# master_jorge3newIMU.net
KiCad netlist of a schematic drawn in EAGLE
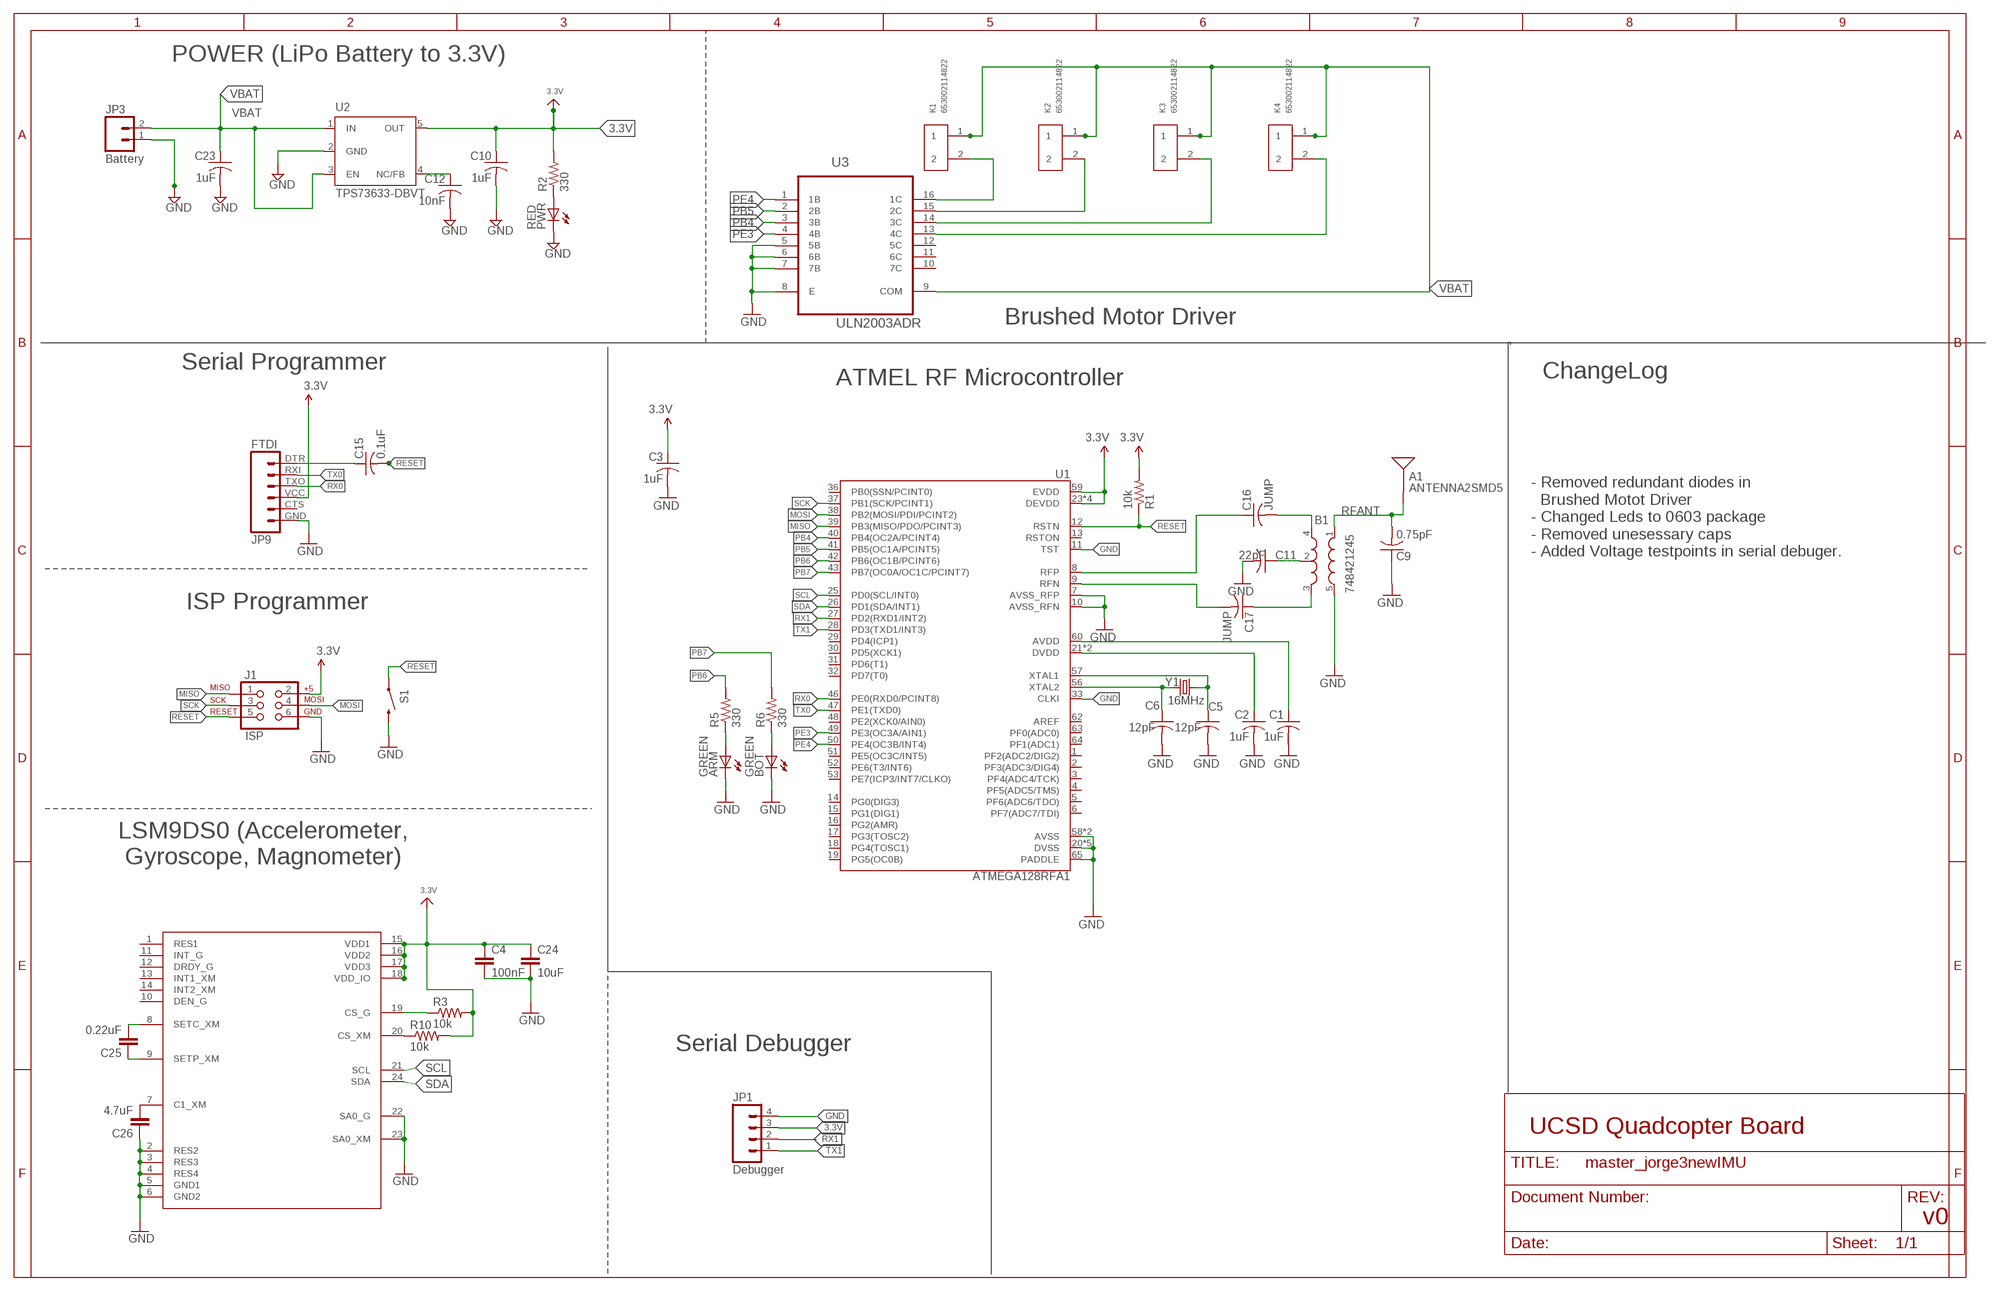
[diagram p0: schematic, sheet 1]

(export (version "E")
  (design (tool "Eeschema 10.0.6"))
  (components
    (comp (ref "A1")
      (value "ANTENNA2SMD5")
      (footprint "eagle-import:ANTENNA-CHIP5")
      (libsource (lib "eagle-import") (part "ANTENNA2SMD5"))
    )
    (comp (ref "ARM")
      (value "GREEN")
      (footprint "eagle-import:CHIP-LED0805")
      (libsource (lib "eagle-import") (part "LEDCHIP-LED0805"))
    )
    (comp (ref "B1")
      (value "748421245")
      (footprint "eagle-import:BALUN")
      (libsource (lib "eagle-import") (part "BALUN0805"))
    )
    (comp (ref "BOT")
      (value "GREEN")
      (footprint "eagle-import:CHIP-LED0805")
      (libsource (lib "eagle-import") (part "LEDCHIP-LED0805"))
    )
    (comp (ref "C1")
      (value "1uF")
      (footprint "eagle-import:C0805")
      (libsource (lib "eagle-import") (part "C-USC0805"))
    )
    (comp (ref "C2")
      (value "1uF")
      (footprint "eagle-import:C0805")
      (libsource (lib "eagle-import") (part "C-USC0805"))
    )
    (comp (ref "C3")
      (value "1uF")
      (footprint "eagle-import:C0805")
      (libsource (lib "eagle-import") (part "C-USC0805"))
    )
    (comp (ref "C4")
      (value "100nF")
      (footprint "eagle-import:0805")
      (libsource (lib "eagle-import") (part "CAP0805"))
    )
    (comp (ref "C5")
      (value "12pF")
      (footprint "eagle-import:C0805")
      (libsource (lib "eagle-import") (part "C-USC0805"))
    )
    (comp (ref "C6")
      (value "12pF")
      (footprint "eagle-import:C0805")
      (libsource (lib "eagle-import") (part "C-USC0805"))
    )
    (comp (ref "C9")
      (value "0.75pF")
      (footprint "eagle-import:C0805")
      (libsource (lib "eagle-import") (part "C-USC0805"))
    )
    (comp (ref "C10")
      (value "1uF")
      (footprint "eagle-import:C0805")
      (libsource (lib "eagle-import") (part "C-USC0805"))
    )
    (comp (ref "C11")
      (value "22pF")
      (footprint "eagle-import:C0805")
      (libsource (lib "eagle-import") (part "C-USC0805"))
    )
    (comp (ref "C12")
      (value "10nF")
      (footprint "eagle-import:C0805")
      (libsource (lib "eagle-import") (part "C-USC0805"))
    )
    (comp (ref "C15")
      (value "0.1uF")
      (footprint "eagle-import:C0805")
      (libsource (lib "eagle-import") (part "C-USC0805"))
    )
    (comp (ref "C16")
      (value "JUMP")
      (footprint "eagle-import:C0805")
      (libsource (lib "eagle-import") (part "C-USC0805"))
    )
    (comp (ref "C17")
      (value "JUMP")
      (footprint "eagle-import:C0805")
      (libsource (lib "eagle-import") (part "C-USC0805"))
    )
    (comp (ref "C23")
      (value "1uF")
      (footprint "eagle-import:C0805")
      (libsource (lib "eagle-import") (part "C-USC0805"))
    )
    (comp (ref "C24")
      (value "10uF")
      (footprint "eagle-import:0805")
      (libsource (lib "eagle-import") (part "CAP0805"))
    )
    (comp (ref "C25")
      (value "0.22uF")
      (footprint "eagle-import:0805")
      (libsource (lib "eagle-import") (part "CAP0805"))
    )
    (comp (ref "C26")
      (value "4.7uF")
      (footprint "eagle-import:0805")
      (libsource (lib "eagle-import") (part "CAP0805"))
    )
    (comp (ref "J1")
      (value "ISP")
      (footprint "eagle-import:2X3-NS")
      (libsource (lib "eagle-import") (part "AVR_SPI_PRG_6NS"))
    )
    (comp (ref "JP1")
      (value "Debugger")
      (footprint "eagle-import:1X04")
      (libsource (lib "eagle-import") (part "M04PTH"))
    )
    (comp (ref "JP3")
      (value "Battery")
      (footprint "eagle-import:1X02")
      (libsource (lib "eagle-import") (part "M02PTH"))
    )
    (comp (ref "JP9")
      (value "FTDI")
      (footprint "eagle-import:FTDI_BASIC")
      (libsource (lib "eagle-import") (part "FTDI_BASICPTH"))
    )
    (comp (ref "K1")
      (value "653002114822")
      (footprint "eagle-import:653002114822")
      (libsource (lib "eagle-import") (part "653002114822"))
    )
    (comp (ref "K2")
      (value "653002114822")
      (footprint "eagle-import:653002114822")
      (libsource (lib "eagle-import") (part "653002114822"))
    )
    (comp (ref "K3")
      (value "653002114822")
      (footprint "eagle-import:653002114822")
      (libsource (lib "eagle-import") (part "653002114822"))
    )
    (comp (ref "K4")
      (value "653002114822")
      (footprint "eagle-import:653002114822")
      (libsource (lib "eagle-import") (part "653002114822"))
    )
    (comp (ref "PWR")
      (value "RED")
      (footprint "eagle-import:CHIP-LED0805")
      (libsource (lib "eagle-import") (part "LEDCHIP-LED0805"))
    )
    (comp (ref "R1")
      (value "10k")
      (footprint "eagle-import:R0805")
      (libsource (lib "eagle-import") (part "R-US_R0805"))
    )
    (comp (ref "R2")
      (value "330")
      (footprint "eagle-import:R0805")
      (libsource (lib "eagle-import") (part "R-US_R0805"))
    )
    (comp (ref "R3")
      (value "10k")
      (footprint "eagle-import:0805")
      (libsource (lib "eagle-import") (part "RESISTOR0805-RES"))
    )
    (comp (ref "R5")
      (value "330")
      (footprint "eagle-import:R0805")
      (libsource (lib "eagle-import") (part "R-US_R0805"))
    )
    (comp (ref "R6")
      (value "330")
      (footprint "eagle-import:R0805")
      (libsource (lib "eagle-import") (part "R-US_R0805"))
    )
    (comp (ref "R10")
      (value "10k")
      (footprint "eagle-import:0805")
      (libsource (lib "eagle-import") (part "RESISTOR0805-RES"))
    )
    (comp (ref "S1")
      (value "SWITCH-MOMENTARY-2SMD")
      (footprint "eagle-import:TACTILE_SWITCH_SMD")
      (libsource (lib "eagle-import") (part "SWITCH-MOMENTARY-2SMD"))
    )
    (comp (ref "U1")
      (value "ATMEGA128RFA1")
      (footprint "eagle-import:QFN-64")
      (libsource (lib "eagle-import") (part "ATMEGA128RFA1"))
    )
    (comp (ref "U2")
      (value "TPS73633-DBVT")
      (footprint "eagle-import:SOT23-DBV")
      (libsource (lib "eagle-import") (part "TPS73633-DBVT"))
    )
    (comp (ref "U3")
      (value "ULN2003ADR")
      (footprint "eagle-import:SOIC127P600X175-16N")
      (libsource (lib "eagle-import") (part "ULN2003ADR"))
    )
    (comp (ref "U4")
      (value "LSM9DS0")
      (footprint "eagle-import:LGA-24")
      (libsource (lib "eagle-import") (part "LSM9DS0"))
    )
    (comp (ref "Y1")
      (value "16MHz")
      (footprint "eagle-import:CRYSTAL-SMD-5X3")
      (libsource (lib "eagle-import") (part "CRYSTAL5X3"))
    )
  )
  (nets
    (net (code "1") (name "/RFANT") (class "Default")
      (node (ref "A1") (pin "FEED") (pinfunction "SIGNAL_FEED") (pintype "bidirectional"))
      (node (ref "B1") (pin "1") (pinfunction "IN_1") (pintype "bidirectional"))
      (node (ref "C9") (pin "2") (pinfunction "2_2") (pintype "passive"))
    )
    (net (code "2") (name "3.3V") (class "Default")
      (node (ref "C10") (pin "1") (pinfunction "1_1") (pintype "passive"))
      (node (ref "C24") (pin "1") (pinfunction "1_1") (pintype "passive"))
      (node (ref "C3") (pin "1") (pinfunction "1_1") (pintype "passive"))
      (node (ref "C4") (pin "1") (pinfunction "1_1") (pintype "passive"))
      (node (ref "J1") (pin "2") (pinfunction "2_2") (pintype "passive"))
      (node (ref "JP1") (pin "3") (pinfunction "3_3") (pintype "passive"))
      (node (ref "JP9") (pin "VCC") (pinfunction "4_VCC") (pintype "passive"))
      (node (ref "R1") (pin "2") (pinfunction "2_2") (pintype "passive"))
      (node (ref "R10") (pin "2") (pinfunction "2_2") (pintype "passive"))
      (node (ref "R2") (pin "2") (pinfunction "2_2") (pintype "passive"))
      (node (ref "R3") (pin "2") (pinfunction "2_2") (pintype "passive"))
      (node (ref "U1") (pin "23") (pinfunction "DEVDD_23") (pintype "bidirectional"))
      (node (ref "U1") (pin "34") (pinfunction "DEVDD_34") (pintype "bidirectional"))
      (node (ref "U1") (pin "44") (pinfunction "DEVDD_44") (pintype "bidirectional"))
      (node (ref "U1") (pin "54") (pinfunction "DEVDD_54") (pintype "bidirectional"))
      (node (ref "U1") (pin "59") (pinfunction "EVDD_59") (pintype "bidirectional"))
      (node (ref "U2") (pin "5") (pinfunction "OUT_5") (pintype "passive"))
      (node (ref "U4") (pin "15") (pinfunction "VDD1_15") (pintype "bidirectional"))
      (node (ref "U4") (pin "16") (pinfunction "VDD2_16") (pintype "bidirectional"))
      (node (ref "U4") (pin "17") (pinfunction "VDD3_17") (pintype "bidirectional"))
      (node (ref "U4") (pin "18") (pinfunction "VDD_IO_18") (pintype "bidirectional"))
    )
    (net (code "3") (name "GND") (class "Default")
      (node (ref "ARM") (pin "C") (pinfunction "C_C") (pintype "passive"))
      (node (ref "B1") (pin "5") (pinfunction "GND_5") (pintype "bidirectional"))
      (node (ref "BOT") (pin "C") (pinfunction "C_C") (pintype "passive"))
      (node (ref "C1") (pin "2") (pinfunction "2_2") (pintype "passive"))
      (node (ref "C10") (pin "2") (pinfunction "2_2") (pintype "passive"))
      (node (ref "C11") (pin "2") (pinfunction "2_2") (pintype "passive"))
      (node (ref "C12") (pin "2") (pinfunction "2_2") (pintype "passive"))
      (node (ref "C2") (pin "2") (pinfunction "2_2") (pintype "passive"))
      (node (ref "C23") (pin "2") (pinfunction "2_2") (pintype "passive"))
      (node (ref "C24") (pin "2") (pinfunction "2_2") (pintype "passive"))
      (node (ref "C26") (pin "1") (pinfunction "1_1") (pintype "passive"))
      (node (ref "C3") (pin "2") (pinfunction "2_2") (pintype "passive"))
      (node (ref "C4") (pin "2") (pinfunction "2_2") (pintype "passive"))
      (node (ref "C5") (pin "2") (pinfunction "2_2") (pintype "passive"))
      (node (ref "C6") (pin "2") (pinfunction "2_2") (pintype "passive"))
      (node (ref "C9") (pin "1") (pinfunction "1_1") (pintype "passive"))
      (node (ref "J1") (pin "6") (pinfunction "6_6") (pintype "passive"))
      (node (ref "JP1") (pin "4") (pinfunction "4_4") (pintype "passive"))
      (node (ref "JP3") (pin "1") (pinfunction "1_1") (pintype "passive"))
      (node (ref "JP9") (pin "GND") (pinfunction "6_GND") (pintype "passive"))
      (node (ref "PWR") (pin "C") (pinfunction "C_C") (pintype "passive"))
      (node (ref "S1") (pin "3") (pinfunction "2_3") (pintype "passive"))
      (node (ref "U1") (pin "10") (pinfunction "AVSS_RFN_10") (pintype "bidirectional"))
      (node (ref "U1") (pin "11") (pinfunction "TST_11") (pintype "bidirectional"))
      (node (ref "U1") (pin "20") (pinfunction "DVSS_20") (pintype "bidirectional"))
      (node (ref "U1") (pin "24") (pinfunction "DVSS_24") (pintype "bidirectional"))
      (node (ref "U1") (pin "33") (pinfunction "CLKI_33") (pintype "bidirectional"))
      (node (ref "U1") (pin "35") (pinfunction "DVSS_35") (pintype "bidirectional"))
      (node (ref "U1") (pin "45") (pinfunction "DVSS_45") (pintype "bidirectional"))
      (node (ref "U1") (pin "55") (pinfunction "DVSS_55") (pintype "bidirectional"))
      (node (ref "U1") (pin "58") (pinfunction "AVSS_58") (pintype "bidirectional"))
      (node (ref "U1") (pin "61") (pinfunction "AVSS_61") (pintype "bidirectional"))
      (node (ref "U1") (pin "65") (pinfunction "PADDLE_65") (pintype "bidirectional"))
      (node (ref "U1") (pin "7") (pinfunction "AVSS_RFP_7") (pintype "bidirectional"))
      (node (ref "U2") (pin "2") (pinfunction "GND_2") (pintype "input"))
      (node (ref "U3") (pin "5") (pinfunction "5B_5") (pintype "input"))
      (node (ref "U3") (pin "6") (pinfunction "6B_6") (pintype "input"))
      (node (ref "U3") (pin "7") (pinfunction "7B_7") (pintype "input"))
      (node (ref "U3") (pin "8") (pinfunction "E_8") (pintype "input"))
      (node (ref "U4") (pin "2") (pinfunction "RES2_2") (pintype "bidirectional"))
      (node (ref "U4") (pin "22") (pinfunction "SA0_G_22") (pintype "bidirectional"))
      (node (ref "U4") (pin "23") (pinfunction "SA0_XM_23") (pintype "bidirectional"))
      (node (ref "U4") (pin "3") (pinfunction "RES3_3") (pintype "bidirectional"))
      (node (ref "U4") (pin "4") (pinfunction "RES4_4") (pintype "bidirectional"))
      (node (ref "U4") (pin "5") (pinfunction "GND1_5") (pintype "bidirectional"))
      (node (ref "U4") (pin "6") (pinfunction "GND2_6") (pintype "bidirectional"))
    )
    (net (code "4") (name "MISO") (class "Default")
      (node (ref "J1") (pin "1") (pinfunction "1_1") (pintype "passive"))
      (node (ref "U1") (pin "39") (pinfunction "PB3(MISO/PDO/PCINT3)_39") (pintype "bidirectional"))
    )
    (net (code "5") (name "MOSI") (class "Default")
      (node (ref "J1") (pin "4") (pinfunction "4_4") (pintype "passive"))
      (node (ref "U1") (pin "38") (pinfunction "PB2(MOSI/PDI/PCINT2)_38") (pintype "bidirectional"))
    )
    (net (code "6") (name "Net-(ARM-PadA)") (class "Default")
      (node (ref "ARM") (pin "A") (pinfunction "A_A") (pintype "passive"))
      (node (ref "R5") (pin "1") (pinfunction "1_1") (pintype "passive"))
    )
    (net (code "7") (name "Net-(B1-GND-Pad2)") (class "Default")
      (node (ref "B1") (pin "2") (pinfunction "GND_2") (pintype "bidirectional"))
      (node (ref "C11") (pin "1") (pinfunction "1_1") (pintype "passive"))
    )
    (net (code "8") (name "Net-(B1-OUT1)") (class "Default")
      (node (ref "B1") (pin "4") (pinfunction "OUT1_4") (pintype "bidirectional"))
      (node (ref "C16") (pin "2") (pinfunction "2_2") (pintype "passive"))
    )
    (net (code "9") (name "Net-(B1-OUT2)") (class "Default")
      (node (ref "B1") (pin "3") (pinfunction "OUT2_3") (pintype "bidirectional"))
      (node (ref "C17") (pin "1") (pinfunction "1_1") (pintype "passive"))
    )
    (net (code "10") (name "Net-(BOT-PadA)") (class "Default")
      (node (ref "BOT") (pin "A") (pinfunction "A_A") (pintype "passive"))
      (node (ref "R6") (pin "1") (pinfunction "1_1") (pintype "passive"))
    )
    (net (code "11") (name "Net-(C2-Pad1)") (class "Default")
      (node (ref "C2") (pin "1") (pinfunction "1_1") (pintype "passive"))
      (node (ref "U1") (pin "21") (pinfunction "DVDD_21") (pintype "bidirectional"))
      (node (ref "U1") (pin "22") (pinfunction "DVDD_22") (pintype "bidirectional"))
    )
    (net (code "12") (name "Net-(JP9-1)") (class "Default")
      (node (ref "C15") (pin "1") (pinfunction "1_1") (pintype "passive"))
      (node (ref "JP9") (pin "DTR") (pinfunction "1_DTR") (pintype "passive"))
    )
    (net (code "13") (name "Net-(PWR-PadA)") (class "Default")
      (node (ref "PWR") (pin "A") (pinfunction "A_A") (pintype "passive"))
      (node (ref "R2") (pin "1") (pinfunction "1_1") (pintype "passive"))
    )
    (net (code "14") (name "Net-(U1-AVDD)") (class "Default")
      (node (ref "C1") (pin "1") (pinfunction "1_1") (pintype "passive"))
      (node (ref "U1") (pin "60") (pinfunction "AVDD_60") (pintype "bidirectional"))
    )
    (net (code "15") (name "Net-(U1-RFN)") (class "Default")
      (node (ref "C17") (pin "2") (pinfunction "2_2") (pintype "passive"))
      (node (ref "U1") (pin "9") (pinfunction "RFN_9") (pintype "bidirectional"))
    )
    (net (code "16") (name "Net-(U1-RFP)") (class "Default")
      (node (ref "C16") (pin "1") (pinfunction "1_1") (pintype "passive"))
      (node (ref "U1") (pin "8") (pinfunction "RFP_8") (pintype "bidirectional"))
    )
    (net (code "17") (name "Net-(U1-XTAL1)") (class "Default")
      (node (ref "C5") (pin "1") (pinfunction "1_1") (pintype "passive"))
      (node (ref "U1") (pin "57") (pinfunction "XTAL1_57") (pintype "bidirectional"))
      (node (ref "Y1") (pin "3") (pinfunction "2_3") (pintype "passive"))
    )
    (net (code "18") (name "Net-(U1-XTAL2)") (class "Default")
      (node (ref "C6") (pin "1") (pinfunction "1_1") (pintype "passive"))
      (node (ref "U1") (pin "56") (pinfunction "XTAL2_56") (pintype "bidirectional"))
      (node (ref "Y1") (pin "1") (pinfunction "1_1") (pintype "passive"))
    )
    (net (code "19") (name "Net-(U2-NC{slash}FB)") (class "Default")
      (node (ref "C12") (pin "1") (pinfunction "1_1") (pintype "passive"))
      (node (ref "U2") (pin "4") (pinfunction "NC/FB_4") (pintype "passive"))
    )
    (net (code "20") (name "Net-(U3-1C)") (class "Default")
      (node (ref "K1") (pin "2") (pinfunction "2_2") (pintype "bidirectional"))
      (node (ref "U3") (pin "16") (pinfunction "1C_16") (pintype "output"))
    )
    (net (code "21") (name "Net-(U3-2C)") (class "Default")
      (node (ref "K2") (pin "2") (pinfunction "2_2") (pintype "bidirectional"))
      (node (ref "U3") (pin "15") (pinfunction "2C_15") (pintype "output"))
    )
    (net (code "22") (name "Net-(U3-3C)") (class "Default")
      (node (ref "K3") (pin "2") (pinfunction "2_2") (pintype "bidirectional"))
      (node (ref "U3") (pin "14") (pinfunction "3C_14") (pintype "output"))
    )
    (net (code "23") (name "Net-(U3-4C)") (class "Default")
      (node (ref "K4") (pin "2") (pinfunction "2_2") (pintype "bidirectional"))
      (node (ref "U3") (pin "13") (pinfunction "4C_13") (pintype "output"))
    )
    (net (code "24") (name "Net-(U4-C1_XM)") (class "Default")
      (node (ref "C26") (pin "2") (pinfunction "2_2") (pintype "passive"))
      (node (ref "U4") (pin "7") (pinfunction "C1_XM_7") (pintype "bidirectional"))
    )
    (net (code "25") (name "Net-(U4-CS_G)") (class "Default")
      (node (ref "R3") (pin "1") (pinfunction "1_1") (pintype "passive"))
      (node (ref "U4") (pin "19") (pinfunction "CS_G_19") (pintype "bidirectional"))
    )
    (net (code "26") (name "Net-(U4-CS_XM)") (class "Default")
      (node (ref "R10") (pin "1") (pinfunction "1_1") (pintype "passive"))
      (node (ref "U4") (pin "20") (pinfunction "CS_XM_20") (pintype "bidirectional"))
    )
    (net (code "27") (name "Net-(U4-SETC_XM)") (class "Default")
      (node (ref "C25") (pin "2") (pinfunction "2_2") (pintype "passive"))
      (node (ref "U4") (pin "8") (pinfunction "SETC_XM_8") (pintype "bidirectional"))
    )
    (net (code "28") (name "Net-(U4-SETP_XM)") (class "Default")
      (node (ref "C25") (pin "1") (pinfunction "1_1") (pintype "passive"))
      (node (ref "U4") (pin "9") (pinfunction "SETP_XM_9") (pintype "bidirectional"))
    )
    (net (code "29") (name "PB4") (class "Default")
      (node (ref "U1") (pin "40") (pinfunction "PB4(OC2A/PCINT4)_40") (pintype "bidirectional"))
      (node (ref "U3") (pin "3") (pinfunction "3B_3") (pintype "input"))
    )
    (net (code "30") (name "PB5") (class "Default")
      (node (ref "U1") (pin "41") (pinfunction "PB5(OC1A/PCINT5)_41") (pintype "bidirectional"))
      (node (ref "U3") (pin "2") (pinfunction "2B_2") (pintype "input"))
    )
    (net (code "31") (name "PB6") (class "Default")
      (node (ref "R5") (pin "2") (pinfunction "2_2") (pintype "passive"))
      (node (ref "U1") (pin "42") (pinfunction "PB6(OC1B/PCINT6)_42") (pintype "bidirectional"))
    )
    (net (code "32") (name "PB7") (class "Default")
      (node (ref "R6") (pin "2") (pinfunction "2_2") (pintype "passive"))
      (node (ref "U1") (pin "43") (pinfunction "PB7(OC0A/OC1C/PCINT7)_43") (pintype "bidirectional"))
    )
    (net (code "33") (name "PE3") (class "Default")
      (node (ref "U1") (pin "49") (pinfunction "PE3(OC3A/AIN1)_49") (pintype "bidirectional"))
      (node (ref "U3") (pin "4") (pinfunction "4B_4") (pintype "input"))
    )
    (net (code "34") (name "PE4") (class "Default")
      (node (ref "U1") (pin "50") (pinfunction "PE4(OC3B/INT4)_50") (pintype "bidirectional"))
      (node (ref "U3") (pin "1") (pinfunction "1B_1") (pintype "input"))
    )
    (net (code "35") (name "RESET") (class "Default")
      (node (ref "C15") (pin "2") (pinfunction "2_2") (pintype "passive"))
      (node (ref "J1") (pin "5") (pinfunction "5_5") (pintype "passive"))
      (node (ref "R1") (pin "1") (pinfunction "1_1") (pintype "passive"))
      (node (ref "S1") (pin "1") (pinfunction "1_1") (pintype "passive"))
      (node (ref "U1") (pin "12") (pinfunction "RSTN_12") (pintype "bidirectional"))
    )
    (net (code "36") (name "RX0") (class "Default")
      (node (ref "JP9") (pin "TXO") (pinfunction "3_TXO") (pintype "passive"))
      (node (ref "U1") (pin "46") (pinfunction "PE0(RXD0/PCINT8)_46") (pintype "bidirectional"))
    )
    (net (code "37") (name "RX1") (class "Default")
      (node (ref "JP1") (pin "2") (pinfunction "2_2") (pintype "passive"))
      (node (ref "U1") (pin "27") (pinfunction "PD2(RXD1/INT2)_27") (pintype "bidirectional"))
    )
    (net (code "38") (name "SCK") (class "Default")
      (node (ref "J1") (pin "3") (pinfunction "3_3") (pintype "passive"))
      (node (ref "U1") (pin "37") (pinfunction "PB1(SCK/PCINT1)_37") (pintype "bidirectional"))
    )
    (net (code "39") (name "SCL") (class "Default")
      (node (ref "U1") (pin "25") (pinfunction "PD0(SCL/INT0)_25") (pintype "bidirectional"))
      (node (ref "U4") (pin "21") (pinfunction "SCL_21") (pintype "bidirectional"))
    )
    (net (code "40") (name "SDA") (class "Default")
      (node (ref "U1") (pin "26") (pinfunction "PD1(SDA/INT1)_26") (pintype "bidirectional"))
      (node (ref "U4") (pin "24") (pinfunction "SDA_24") (pintype "bidirectional"))
    )
    (net (code "41") (name "TX0") (class "Default")
      (node (ref "JP9") (pin "RXI") (pinfunction "2_RXI") (pintype "passive"))
      (node (ref "U1") (pin "47") (pinfunction "PE1(TXD0)_47") (pintype "bidirectional"))
    )
    (net (code "42") (name "TX1") (class "Default")
      (node (ref "JP1") (pin "1") (pinfunction "1_1") (pintype "passive"))
      (node (ref "U1") (pin "28") (pinfunction "PD3(TXD1/INT3)_28") (pintype "bidirectional"))
    )
    (net (code "43") (name "VBAT") (class "Default")
      (node (ref "C23") (pin "1") (pinfunction "1_1") (pintype "passive"))
      (node (ref "JP3") (pin "2") (pinfunction "2_2") (pintype "passive"))
      (node (ref "K1") (pin "1") (pinfunction "1_1") (pintype "bidirectional"))
      (node (ref "K2") (pin "1") (pinfunction "1_1") (pintype "bidirectional"))
      (node (ref "K3") (pin "1") (pinfunction "1_1") (pintype "bidirectional"))
      (node (ref "K4") (pin "1") (pinfunction "1_1") (pintype "bidirectional"))
      (node (ref "U2") (pin "1") (pinfunction "IN_1") (pintype "input"))
      (node (ref "U2") (pin "3") (pinfunction "EN_3") (pintype "power_in"))
      (node (ref "U3") (pin "9") (pinfunction "COM_9") (pintype "output"))
    )
    (net (code "44") (name "unconnected-(JP9-5-PadCTS)") (class "Default")
      (node (ref "JP9") (pin "CTS") (pinfunction "5_CTS") (pintype "passive"))
    )
    (net (code "45") (name "unconnected-(U1-AREF-Pad62)") (class "Default")
      (node (ref "U1") (pin "62") (pinfunction "AREF_62") (pintype "bidirectional"))
    )
    (net (code "46") (name "unconnected-(U1-PB0(SSN{slash}PCINT0)-Pad36)") (class "Default")
      (node (ref "U1") (pin "36") (pinfunction "PB0(SSN/PCINT0)_36") (pintype "bidirectional"))
    )
    (net (code "47") (name "unconnected-(U1-PD4(ICP1)-Pad29)") (class "Default")
      (node (ref "U1") (pin "29") (pinfunction "PD4(ICP1)_29") (pintype "bidirectional"))
    )
    (net (code "48") (name "unconnected-(U1-PD5(XCK1)-Pad30)") (class "Default")
      (node (ref "U1") (pin "30") (pinfunction "PD5(XCK1)_30") (pintype "bidirectional"))
    )
    (net (code "49") (name "unconnected-(U1-PD6(T1)-Pad31)") (class "Default")
      (node (ref "U1") (pin "31") (pinfunction "PD6(T1)_31") (pintype "bidirectional"))
    )
    (net (code "50") (name "unconnected-(U1-PD7(T0)-Pad32)") (class "Default")
      (node (ref "U1") (pin "32") (pinfunction "PD7(T0)_32") (pintype "bidirectional"))
    )
    (net (code "51") (name "unconnected-(U1-PE2(XCK0{slash}AIN0)-Pad48)") (class "Default")
      (node (ref "U1") (pin "48") (pinfunction "PE2(XCK0/AIN0)_48") (pintype "bidirectional"))
    )
    (net (code "52") (name "unconnected-(U1-PE5(OC3C{slash}INT5)-Pad51)") (class "Default")
      (node (ref "U1") (pin "51") (pinfunction "PE5(OC3C/INT5)_51") (pintype "bidirectional"))
    )
    (net (code "53") (name "unconnected-(U1-PE6(T3{slash}INT6)-Pad52)") (class "Default")
      (node (ref "U1") (pin "52") (pinfunction "PE6(T3/INT6)_52") (pintype "bidirectional"))
    )
    (net (code "54") (name "unconnected-(U1-PE7(ICP3{slash}INT7{slash}CLKO)-Pad53)") (class "Default")
      (node (ref "U1") (pin "53") (pinfunction "PE7(ICP3/INT7/CLKO)_53") (pintype "bidirectional"))
    )
    (net (code "55") (name "unconnected-(U1-PF0(ADC0)-Pad63)") (class "Default")
      (node (ref "U1") (pin "63") (pinfunction "PF0(ADC0)_63") (pintype "bidirectional"))
    )
    (net (code "56") (name "unconnected-(U1-PF1(ADC1)-Pad64)") (class "Default")
      (node (ref "U1") (pin "64") (pinfunction "PF1(ADC1)_64") (pintype "bidirectional"))
    )
    (net (code "57") (name "unconnected-(U1-PF2(ADC2{slash}DIG2)-Pad1)") (class "Default")
      (node (ref "U1") (pin "1") (pinfunction "PF2(ADC2/DIG2)_1") (pintype "bidirectional"))
    )
    (net (code "58") (name "unconnected-(U1-PF3(ADC3{slash}DIG4)-Pad2)") (class "Default")
      (node (ref "U1") (pin "2") (pinfunction "PF3(ADC3/DIG4)_2") (pintype "bidirectional"))
    )
    (net (code "59") (name "unconnected-(U1-PF4(ADC4{slash}TCK)-Pad3)") (class "Default")
      (node (ref "U1") (pin "3") (pinfunction "PF4(ADC4/TCK)_3") (pintype "bidirectional"))
    )
    (net (code "60") (name "unconnected-(U1-PF5(ADC5{slash}TMS)-Pad4)") (class "Default")
      (node (ref "U1") (pin "4") (pinfunction "PF5(ADC5/TMS)_4") (pintype "bidirectional"))
    )
    (net (code "61") (name "unconnected-(U1-PF6(ADC6{slash}TDO)-Pad5)") (class "Default")
      (node (ref "U1") (pin "5") (pinfunction "PF6(ADC6/TDO)_5") (pintype "bidirectional"))
    )
    (net (code "62") (name "unconnected-(U1-PF7(ADC7{slash}TDI)-Pad6)") (class "Default")
      (node (ref "U1") (pin "6") (pinfunction "PF7(ADC7/TDI)_6") (pintype "bidirectional"))
    )
    (net (code "63") (name "unconnected-(U1-PG0(DIG3)-Pad14)") (class "Default")
      (node (ref "U1") (pin "14") (pinfunction "PG0(DIG3)_14") (pintype "bidirectional"))
    )
    (net (code "64") (name "unconnected-(U1-PG1(DIG1)-Pad15)") (class "Default")
      (node (ref "U1") (pin "15") (pinfunction "PG1(DIG1)_15") (pintype "bidirectional"))
    )
    (net (code "65") (name "unconnected-(U1-PG2(AMR)-Pad16)") (class "Default")
      (node (ref "U1") (pin "16") (pinfunction "PG2(AMR)_16") (pintype "bidirectional"))
    )
    (net (code "66") (name "unconnected-(U1-PG3(TOSC2)-Pad17)") (class "Default")
      (node (ref "U1") (pin "17") (pinfunction "PG3(TOSC2)_17") (pintype "bidirectional"))
    )
    (net (code "67") (name "unconnected-(U1-PG4(TOSC1)-Pad18)") (class "Default")
      (node (ref "U1") (pin "18") (pinfunction "PG4(TOSC1)_18") (pintype "bidirectional"))
    )
    (net (code "68") (name "unconnected-(U1-PG5(OC0B)-Pad19)") (class "Default")
      (node (ref "U1") (pin "19") (pinfunction "PG5(OC0B)_19") (pintype "bidirectional"))
    )
    (net (code "69") (name "unconnected-(U1-RSTON-Pad13)") (class "Default")
      (node (ref "U1") (pin "13") (pinfunction "RSTON_13") (pintype "bidirectional"))
    )
    (net (code "70") (name "unconnected-(U3-5C-Pad12)") (class "Default")
      (node (ref "U3") (pin "12") (pinfunction "5C_12") (pintype "output"))
    )
    (net (code "71") (name "unconnected-(U3-6C-Pad11)") (class "Default")
      (node (ref "U3") (pin "11") (pinfunction "6C_11") (pintype "output"))
    )
    (net (code "72") (name "unconnected-(U3-7C-Pad10)") (class "Default")
      (node (ref "U3") (pin "10") (pinfunction "7C_10") (pintype "output"))
    )
    (net (code "73") (name "unconnected-(U4-DEN_G-Pad10)") (class "Default")
      (node (ref "U4") (pin "10") (pinfunction "DEN_G_10") (pintype "bidirectional"))
    )
    (net (code "74") (name "unconnected-(U4-DRDY_G-Pad12)") (class "Default")
      (node (ref "U4") (pin "12") (pinfunction "DRDY_G_12") (pintype "bidirectional"))
    )
    (net (code "75") (name "unconnected-(U4-INT1_XM-Pad13)") (class "Default")
      (node (ref "U4") (pin "13") (pinfunction "INT1_XM_13") (pintype "bidirectional"))
    )
    (net (code "76") (name "unconnected-(U4-INT2_XM-Pad14)") (class "Default")
      (node (ref "U4") (pin "14") (pinfunction "INT2_XM_14") (pintype "bidirectional"))
    )
    (net (code "77") (name "unconnected-(U4-INT_G-Pad11)") (class "Default")
      (node (ref "U4") (pin "11") (pinfunction "INT_G_11") (pintype "bidirectional"))
    )
    (net (code "78") (name "unconnected-(U4-RES1-Pad1)") (class "Default")
      (node (ref "U4") (pin "1") (pinfunction "RES1_1") (pintype "bidirectional"))
    )
  )
)
